# roco1044.net
KiCad netlist of a schematic drawn in EAGLE
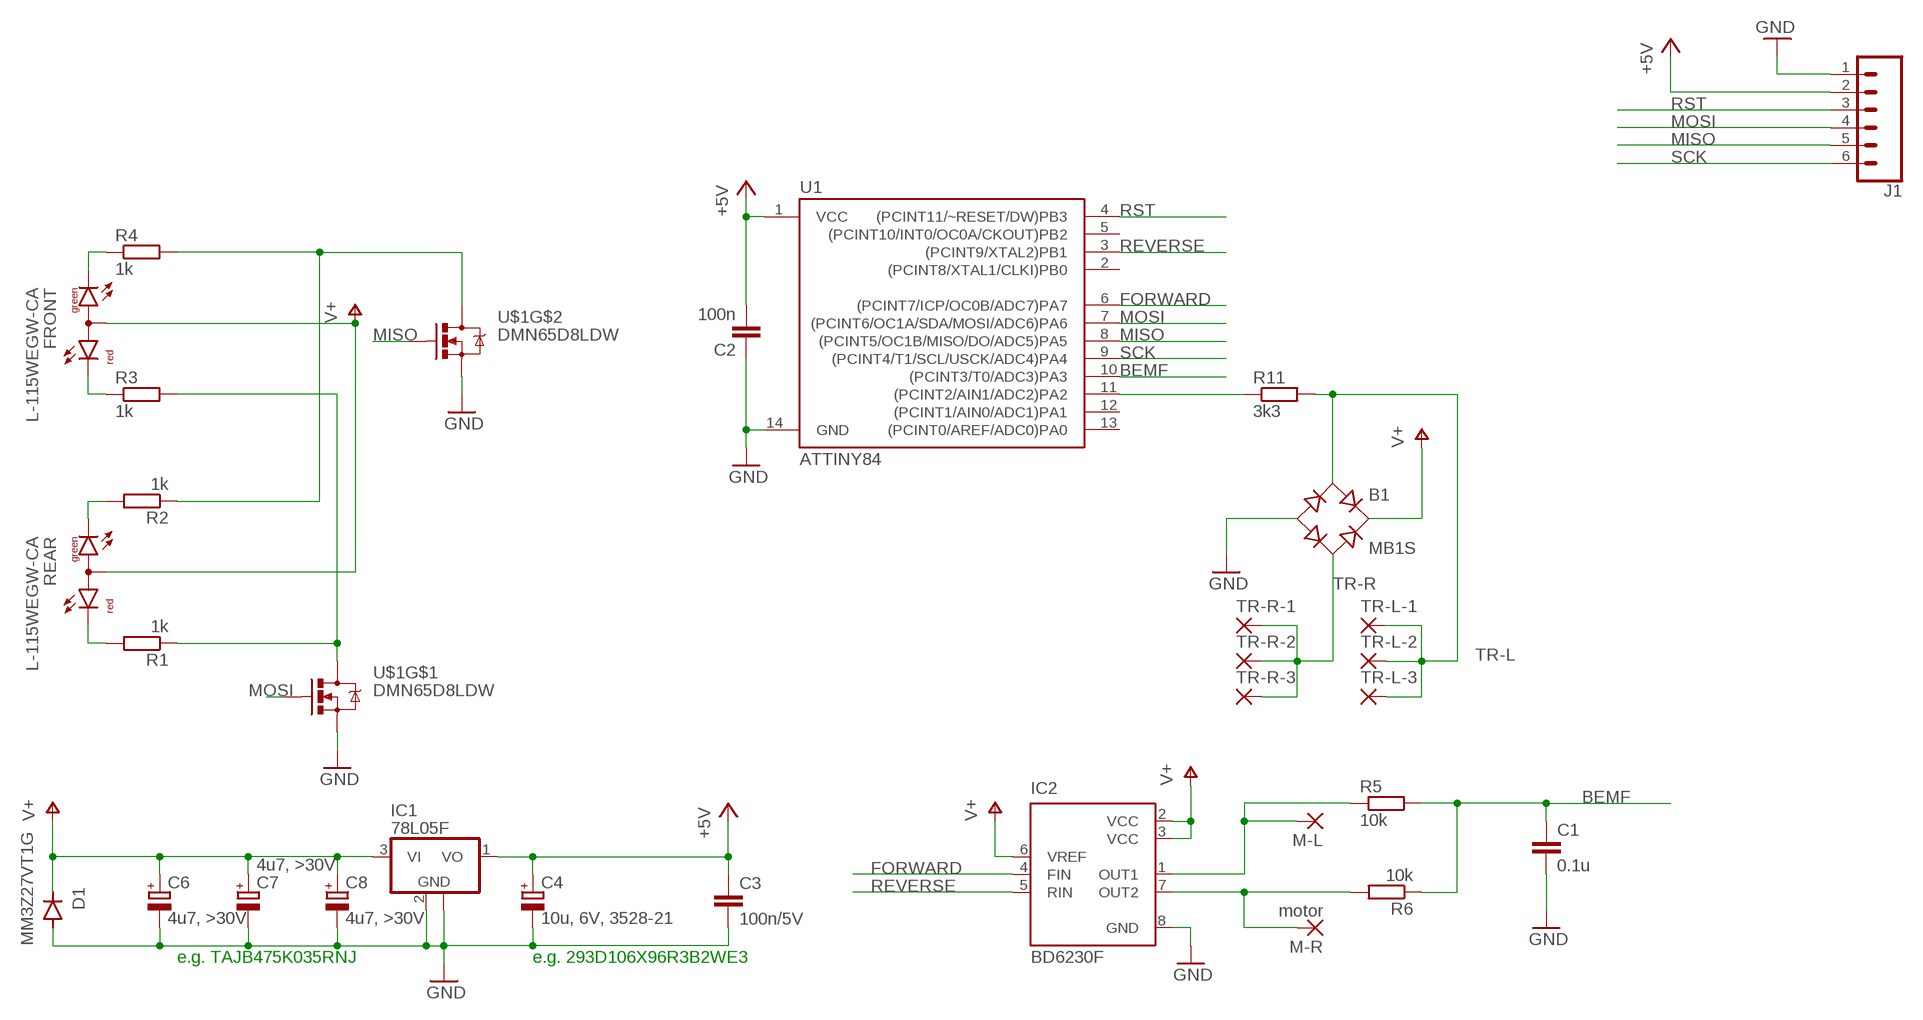
[diagram p0: schematic, sheet 1]

(export (version "E")
  (design (tool "Eeschema 10.0.6"))
  (components
    (comp (ref "B1")
      (value "MB1S")
      (footprint "eagle-import:SOIC-4")
      (libsource (lib "eagle-import") (part "MBS1"))
    )
    (comp (ref "C1")
      (value "0.1u")
      (footprint "eagle-import:C0805")
      (libsource (lib "eagle-import") (part "resistor_348_C-EUC0805"))
    )
    (comp (ref "C2")
      (value "100n")
      (footprint "eagle-import:C0805")
      (libsource (lib "eagle-import") (part "C-EUC0805"))
    )
    (comp (ref "C3")
      (value "100n/5V")
      (footprint "eagle-import:C0805")
      (libsource (lib "eagle-import") (part "C-EUC0805"))
    )
    (comp (ref "C4")
      (value "10u, 6V, 3528-21")
      (footprint "eagle-import:CT3528")
      (libsource (lib "eagle-import") (part "CPOL-EUCT3528"))
    )
    (comp (ref "C6")
      (value "4u7, >30V")
      (footprint "eagle-import:CT3528")
      (libsource (lib "eagle-import") (part "CPOL-EUCT3528"))
    )
    (comp (ref "C7")
      (value "4u7, >30V")
      (footprint "eagle-import:CT3528")
      (libsource (lib "eagle-import") (part "CPOL-EUCT3528"))
    )
    (comp (ref "C8")
      (value "4u7, >30V")
      (footprint "eagle-import:CT3528")
      (libsource (lib "eagle-import") (part "CPOL-EUCT3528"))
    )
    (comp (ref "D1")
      (value "MM3Z27VT1G")
      (footprint "eagle-import:SOD323-R")
      (libsource (lib "eagle-import") (part "DIODE-SOD323-R"))
    )
    (comp (ref "FRONT")
      (value "L-115WEGW-CA")
      (footprint "eagle-import:DUOLED-A-3MM")
      (libsource (lib "eagle-import") (part "L-115WEGW-CA"))
    )
    (comp (ref "IC1")
      (value "78L05F")
      (footprint "eagle-import:SOT89")
      (libsource (lib "eagle-import") (part "78LF05"))
    )
    (comp (ref "IC2")
      (value "BD6230F")
      (footprint "eagle-import:SOP8")
      (fields (field (name "MPN") "BD6230F-E2"))
      (libsource (lib "eagle-import") (part "BD623F0"))
    )
    (comp (ref "J1")
      (value "CONN_061.27MM")
      (footprint "eagle-import:1X06_1.27MM")
      (libsource (lib "eagle-import") (part "CONN_061.27MM"))
    )
    (comp (ref "M-L")
      (value "SMD5")
      (footprint "eagle-import:SMD2,54-5,08")
      (libsource (lib "eagle-import") (part "SMD5"))
    )
    (comp (ref "M-R")
      (value "motor")
      (footprint "eagle-import:SMD2,54-5,08")
      (libsource (lib "eagle-import") (part "SMD5"))
    )
    (comp (ref "R1")
      (value "1k")
      (footprint "eagle-import:R0603")
      (libsource (lib "eagle-import") (part "R-EU_R0603"))
    )
    (comp (ref "R2")
      (value "1k")
      (footprint "eagle-import:R0603")
      (libsource (lib "eagle-import") (part "R-EU_R0603"))
    )
    (comp (ref "R3")
      (value "1k")
      (footprint "eagle-import:R0603")
      (libsource (lib "eagle-import") (part "R-EU_R0603"))
    )
    (comp (ref "R4")
      (value "1k")
      (footprint "eagle-import:R0603")
      (libsource (lib "eagle-import") (part "R-EU_R0603"))
    )
    (comp (ref "R5")
      (value "10k")
      (footprint "eagle-import:R0603")
      (libsource (lib "eagle-import") (part "R-EU_R0603"))
    )
    (comp (ref "R6")
      (value "10k")
      (footprint "eagle-import:R0603")
      (libsource (lib "eagle-import") (part "R-EU_R0603"))
    )
    (comp (ref "R11")
      (value "3k3")
      (footprint "eagle-import:R0603")
      (libsource (lib "eagle-import") (part "R-EU_R0603"))
    )
    (comp (ref "REAR")
      (value "L-115WEGW-CA")
      (footprint "eagle-import:DUOLED-A-3MM")
      (libsource (lib "eagle-import") (part "L-115WEGW-CA"))
    )
    (comp (ref "TR-L-1")
      (value "SMD5")
      (footprint "eagle-import:SMD2,54-5,08")
      (libsource (lib "eagle-import") (part "SMD5"))
    )
    (comp (ref "TR-L-2")
      (value "SMD5")
      (footprint "eagle-import:SMD2,54-5,08")
      (libsource (lib "eagle-import") (part "SMD5"))
    )
    (comp (ref "TR-L-3")
      (value "SMD5")
      (footprint "eagle-import:SMD2,54-5,08")
      (libsource (lib "eagle-import") (part "SMD5"))
    )
    (comp (ref "TR-R-1")
      (value "SMD5")
      (footprint "eagle-import:SMD2,54-5,08")
      (libsource (lib "eagle-import") (part "SMD5"))
    )
    (comp (ref "TR-R-2")
      (value "SMD5")
      (footprint "eagle-import:SMD2,54-5,08")
      (libsource (lib "eagle-import") (part "SMD5"))
    )
    (comp (ref "TR-R-3")
      (value "SMD5")
      (footprint "eagle-import:SMD2,54-5,08")
      (libsource (lib "eagle-import") (part "SMD5"))
    )
    (comp (ref "U$1")
      (value "DMN65D8LDW")
      (footprint "eagle-import:SOT363")
      (libsource (lib "eagle-import") (part "DMN65D8LDW"))
    )
    (comp (ref "U1")
      (value "ATTINY84")
      (footprint "eagle-import:SO14")
      (libsource (lib "eagle-import") (part "ATTINY84"))
    )
  )
  (nets
    (net (code "1") (name "+5V") (class "Default")
      (node (ref "C2") (pin "2") (pinfunction "2_2") (pintype "passive"))
      (node (ref "C3") (pin "1") (pinfunction "1_1") (pintype "passive"))
      (node (ref "C4") (pin "+") (pinfunction "+_+") (pintype "passive"))
      (node (ref "IC1") (pin "1") (pinfunction "VO_1") (pintype "passive"))
      (node (ref "J1") (pin "2") (pinfunction "2_2") (pintype "passive"))
      (node (ref "U1") (pin "1") (pinfunction "VCC_1") (pintype "bidirectional"))
    )
    (net (code "2") (name "/BEMF") (class "Default")
      (node (ref "C1") (pin "1") (pinfunction "1_1") (pintype "passive"))
      (node (ref "R5") (pin "2") (pinfunction "2_2") (pintype "passive"))
      (node (ref "R6") (pin "1") (pinfunction "1_1") (pintype "passive"))
      (node (ref "U1") (pin "10") (pinfunction "(PCINT3/T0/ADC3)PA3_10") (pintype "bidirectional"))
    )
    (net (code "3") (name "/FORWARD") (class "Default")
      (node (ref "IC2") (pin "4") (pinfunction "FIN_4") (pintype "input"))
      (node (ref "U1") (pin "6") (pinfunction "(PCINT7/ICP/OC0B/ADC7)PA7_6") (pintype "bidirectional"))
    )
    (net (code "4") (name "/MISO") (class "Default")
      (node (ref "J1") (pin "5") (pinfunction "5_5") (pintype "passive"))
      (node (ref "U$1") (pin "P$5") (pinfunction "G_P$5") (pintype "passive"))
      (node (ref "U1") (pin "8") (pinfunction "(PCINT5/OC1B/MISO/DO/ADC5)PA5_8") (pintype "bidirectional"))
    )
    (net (code "5") (name "/MOSI") (class "Default")
      (node (ref "J1") (pin "4") (pinfunction "4_4") (pintype "passive"))
      (node (ref "U$1") (pin "P$2") (pinfunction "G_P$2") (pintype "passive"))
      (node (ref "U1") (pin "7") (pinfunction "(PCINT6/OC1A/SDA/MOSI/ADC6)PA6_7") (pintype "bidirectional"))
    )
    (net (code "6") (name "/REVERSE") (class "Default")
      (node (ref "IC2") (pin "5") (pinfunction "RIN_5") (pintype "input"))
      (node (ref "U1") (pin "3") (pinfunction "(PCINT9/XTAL2)PB1_3") (pintype "bidirectional"))
    )
    (net (code "7") (name "/RST") (class "Default")
      (node (ref "J1") (pin "3") (pinfunction "3_3") (pintype "passive"))
      (node (ref "U1") (pin "4") (pinfunction "(PCINT11/~{RESET/DW})PB3_4") (pintype "bidirectional"))
    )
    (net (code "8") (name "/SCK") (class "Default")
      (node (ref "J1") (pin "6") (pinfunction "6_6") (pintype "passive"))
      (node (ref "U1") (pin "9") (pinfunction "(PCINT4/T1/SCL/USCK/ADC4)PA4_9") (pintype "bidirectional"))
    )
    (net (code "9") (name "/TR-L") (class "Default")
      (node (ref "B1") (pin "~1") (pinfunction "AC1_~1") (pintype "passive"))
      (node (ref "R11") (pin "2") (pinfunction "2_2") (pintype "passive"))
      (node (ref "TR-L-1") (pin "1") (pinfunction "P_1") (pintype "passive"))
      (node (ref "TR-L-2") (pin "1") (pinfunction "P_1") (pintype "passive"))
      (node (ref "TR-L-3") (pin "1") (pinfunction "P_1") (pintype "passive"))
    )
    (net (code "10") (name "/TR-R") (class "Default")
      (node (ref "B1") (pin "~2") (pinfunction "AC2_~2") (pintype "passive"))
      (node (ref "TR-R-1") (pin "1") (pinfunction "P_1") (pintype "passive"))
      (node (ref "TR-R-2") (pin "1") (pinfunction "P_1") (pintype "passive"))
      (node (ref "TR-R-3") (pin "1") (pinfunction "P_1") (pintype "passive"))
    )
    (net (code "11") (name "GND") (class "Default")
      (node (ref "B1") (pin "-") (pinfunction "-_-") (pintype "passive"))
      (node (ref "C1") (pin "2") (pinfunction "2_2") (pintype "passive"))
      (node (ref "C2") (pin "1") (pinfunction "1_1") (pintype "passive"))
      (node (ref "C3") (pin "2") (pinfunction "2_2") (pintype "passive"))
      (node (ref "C4") (pin "-") (pinfunction "-_-") (pintype "passive"))
      (node (ref "C6") (pin "-") (pinfunction "-_-") (pintype "passive"))
      (node (ref "C7") (pin "-") (pinfunction "-_-") (pintype "passive"))
      (node (ref "C8") (pin "-") (pinfunction "-_-") (pintype "passive"))
      (node (ref "D1") (pin "A") (pinfunction "A_A") (pintype "passive"))
      (node (ref "IC1") (pin "2") (pinfunction "GND_2") (pintype "passive"))
      (node (ref "IC1") (pin "2@1") (pinfunction "GND_2@1") (pintype "passive"))
      (node (ref "IC2") (pin "8") (pinfunction "GND_8") (pintype "power_in"))
      (node (ref "J1") (pin "1") (pinfunction "1_1") (pintype "passive"))
      (node (ref "U$1") (pin "P$3") (pinfunction "S_P$3") (pintype "passive"))
      (node (ref "U$1") (pin "P$6") (pinfunction "S_P$6") (pintype "passive"))
      (node (ref "U1") (pin "14") (pinfunction "GND_14") (pintype "bidirectional"))
    )
    (net (code "12") (name "Net-(FRONT-CG)") (class "Default")
      (node (ref "FRONT") (pin "1") (pinfunction "CG_1") (pintype "passive"))
      (node (ref "R4") (pin "1") (pinfunction "1_1") (pintype "passive"))
    )
    (net (code "13") (name "Net-(FRONT-CR)") (class "Default")
      (node (ref "FRONT") (pin "3") (pinfunction "CR_3") (pintype "passive"))
      (node (ref "R3") (pin "1") (pinfunction "1_1") (pintype "passive"))
    )
    (net (code "14") (name "Net-(IC2-OUT1)") (class "Default")
      (node (ref "IC2") (pin "1") (pinfunction "OUT1_1") (pintype "output"))
      (node (ref "M-L") (pin "1") (pinfunction "P_1") (pintype "passive"))
      (node (ref "R5") (pin "1") (pinfunction "1_1") (pintype "passive"))
    )
    (net (code "15") (name "Net-(IC2-OUT2)") (class "Default")
      (node (ref "IC2") (pin "7") (pinfunction "OUT2_7") (pintype "output"))
      (node (ref "M-R") (pin "1") (pinfunction "P_1") (pintype "passive"))
      (node (ref "R6") (pin "2") (pinfunction "2_2") (pintype "passive"))
    )
    (net (code "16") (name "Net-(REAR-CG)") (class "Default")
      (node (ref "R2") (pin "2") (pinfunction "2_2") (pintype "passive"))
      (node (ref "REAR") (pin "1") (pinfunction "CG_1") (pintype "passive"))
    )
    (net (code "17") (name "Net-(REAR-CR)") (class "Default")
      (node (ref "R1") (pin "2") (pinfunction "2_2") (pintype "passive"))
      (node (ref "REAR") (pin "3") (pinfunction "CR_3") (pintype "passive"))
    )
    (net (code "18") (name "Net-(U$1A-D)") (class "Default")
      (node (ref "R1") (pin "1") (pinfunction "1_1") (pintype "passive"))
      (node (ref "R3") (pin "2") (pinfunction "2_2") (pintype "passive"))
      (node (ref "U$1") (pin "P$4") (pinfunction "D_P$4") (pintype "passive"))
    )
    (net (code "19") (name "Net-(U$1B-D)") (class "Default")
      (node (ref "R2") (pin "1") (pinfunction "1_1") (pintype "passive"))
      (node (ref "R4") (pin "2") (pinfunction "2_2") (pintype "passive"))
      (node (ref "U$1") (pin "P$1") (pinfunction "D_P$1") (pintype "passive"))
    )
    (net (code "20") (name "Net-(U1-(PCINT2{slash}AIN1{slash}ADC2)PA2)") (class "Default")
      (node (ref "R11") (pin "1") (pinfunction "1_1") (pintype "passive"))
      (node (ref "U1") (pin "11") (pinfunction "(PCINT2/AIN1/ADC2)PA2_11") (pintype "bidirectional"))
    )
    (net (code "21") (name "V+") (class "Default")
      (node (ref "B1") (pin "+") (pinfunction "+_+") (pintype "passive"))
      (node (ref "C6") (pin "+") (pinfunction "+_+") (pintype "passive"))
      (node (ref "C7") (pin "+") (pinfunction "+_+") (pintype "passive"))
      (node (ref "C8") (pin "+") (pinfunction "+_+") (pintype "passive"))
      (node (ref "D1") (pin "C") (pinfunction "C_C") (pintype "passive"))
      (node (ref "FRONT") (pin "2") (pinfunction "A_2") (pintype "passive"))
      (node (ref "IC1") (pin "3") (pinfunction "VI_3") (pintype "input"))
      (node (ref "IC2") (pin "2") (pinfunction "VCC_2") (pintype "power_in"))
      (node (ref "IC2") (pin "3") (pinfunction "VCC_3") (pintype "power_in"))
      (node (ref "IC2") (pin "6") (pinfunction "VREF_6") (pintype "passive"))
      (node (ref "REAR") (pin "2") (pinfunction "A_2") (pintype "passive"))
    )
    (net (code "22") (name "unconnected-(U1-(PCINT0{slash}AREF{slash}ADC0)PA0-Pad13)") (class "Default")
      (node (ref "U1") (pin "13") (pinfunction "(PCINT0/AREF/ADC0)PA0_13") (pintype "bidirectional"))
    )
    (net (code "23") (name "unconnected-(U1-(PCINT1{slash}AIN0{slash}ADC1)PA1-Pad12)") (class "Default")
      (node (ref "U1") (pin "12") (pinfunction "(PCINT1/AIN0/ADC1)PA1_12") (pintype "bidirectional"))
    )
    (net (code "24") (name "unconnected-(U1-(PCINT8{slash}XTAL1{slash}CLKI)PB0-Pad2)") (class "Default")
      (node (ref "U1") (pin "2") (pinfunction "(PCINT8/XTAL1/CLKI)PB0_2") (pintype "bidirectional"))
    )
    (net (code "25") (name "unconnected-(U1-(PCINT10{slash}INT0{slash}OC0A{slash}CKOUT)PB2-Pad5)") (class "Default")
      (node (ref "U1") (pin "5") (pinfunction "(PCINT10/INT0/OC0A/CKOUT)PB2_5") (pintype "bidirectional"))
    )
  )
)
